# Sparkfun_LilyPad-Switched-Battery.net
KiCad netlist of a schematic drawn in EAGLE
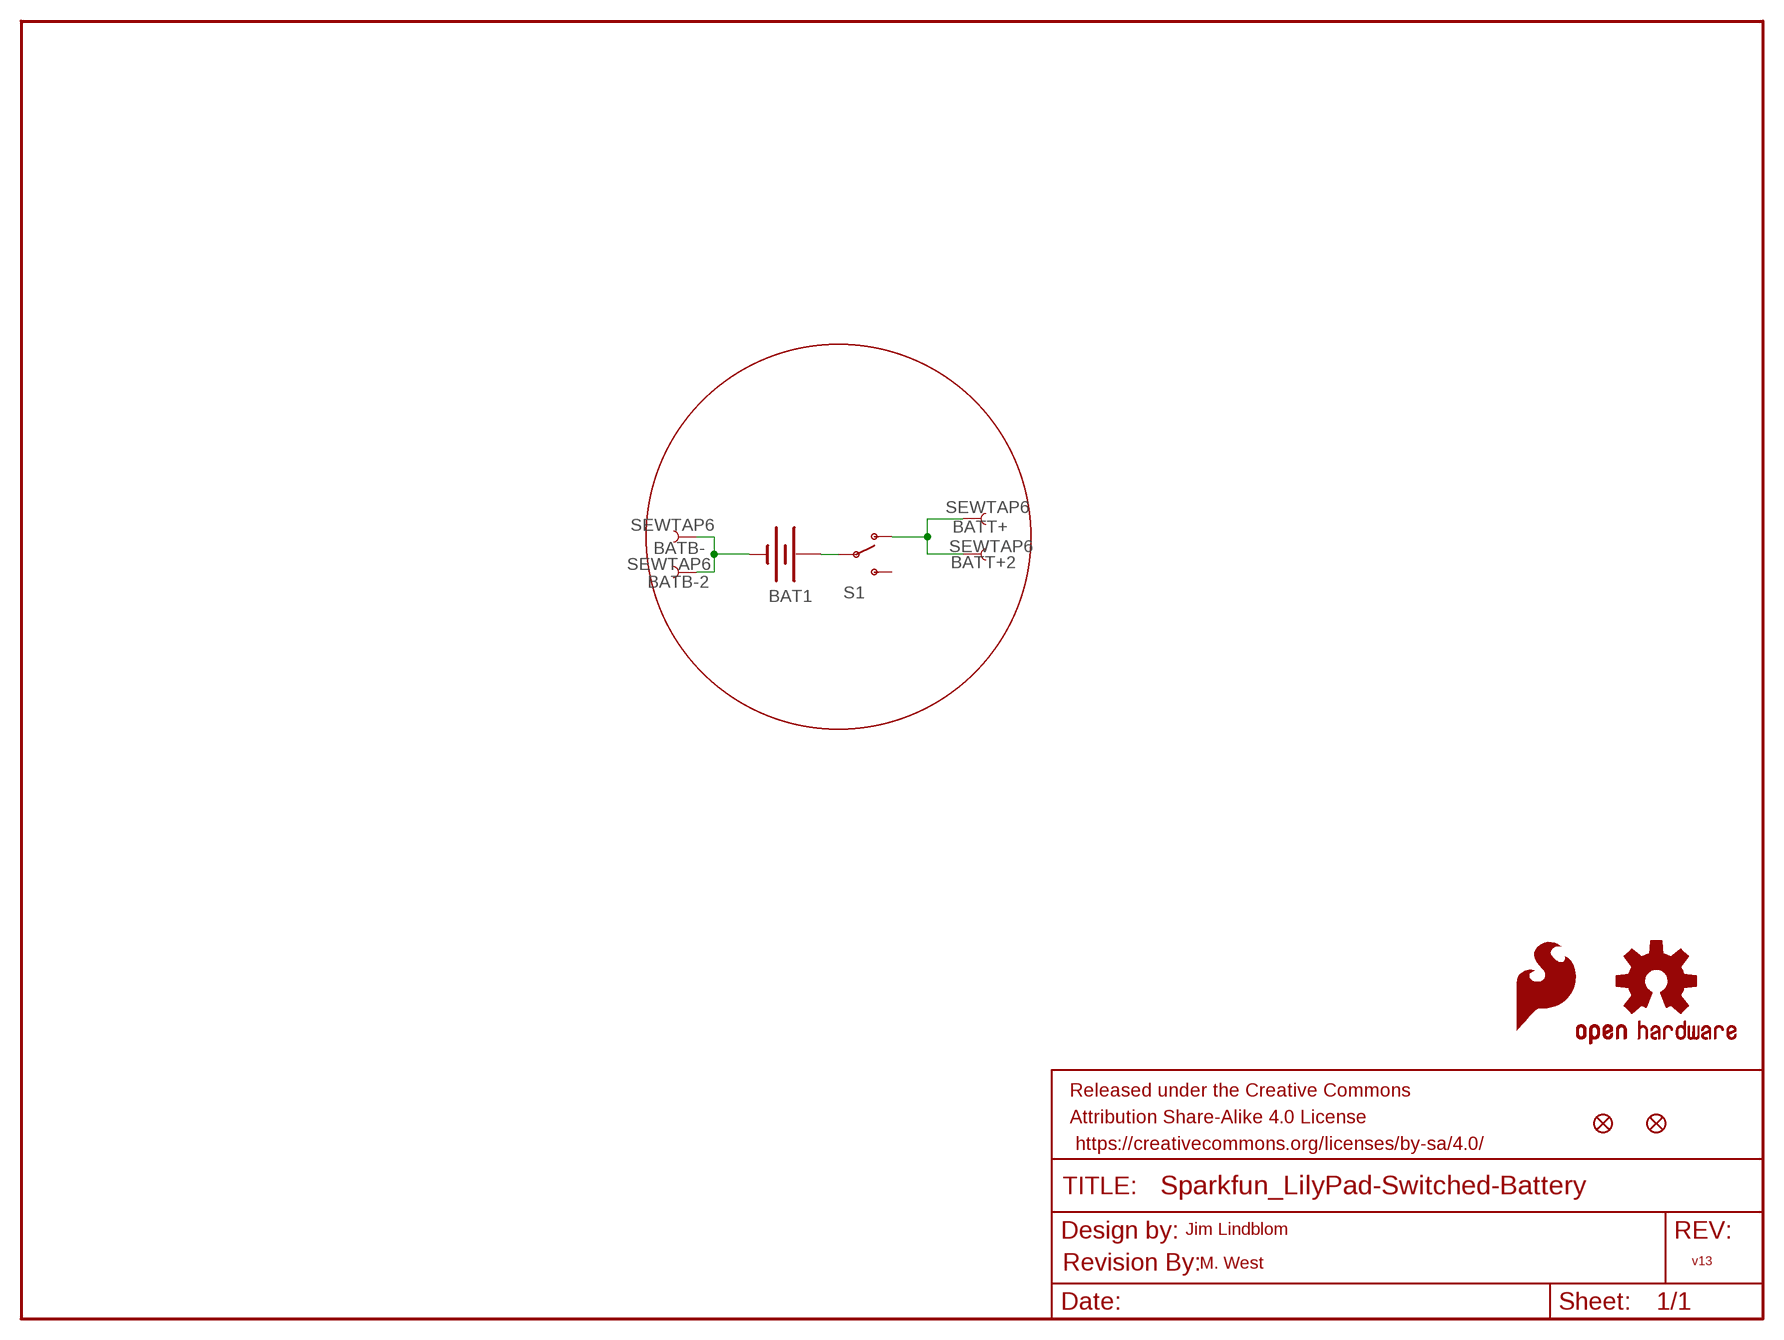
[diagram p0: schematic, sheet 1]

(export (version "E")
  (design (tool "Eeschema 10.0.6"))
  (components
    (comp (ref "BAT1")
      (value "20mm coincell")
      (footprint "eagle-import:BATTCON_20MM_4LEGS")
      (libsource (lib "eagle-import") (part "BATTERY20MM_4LEGS"))
    )
    (comp (ref "BATB-")
      (value "SEWTAP6")
      (footprint "eagle-import:PETAL-SMALL-2SIDE")
      (libsource (lib "eagle-import") (part "SEWTAP6"))
    )
    (comp (ref "BATB-2")
      (value "SEWTAP6")
      (footprint "eagle-import:PETAL-SMALL-2SIDE")
      (libsource (lib "eagle-import") (part "SEWTAP6"))
    )
    (comp (ref "BATT+")
      (value "SEWTAP6")
      (footprint "eagle-import:PETAL-SMALL-2SIDE")
      (libsource (lib "eagle-import") (part "SEWTAP6"))
    )
    (comp (ref "BATT+2")
      (value "SEWTAP6")
      (footprint "eagle-import:PETAL-SMALL-2SIDE")
      (libsource (lib "eagle-import") (part "SEWTAP6"))
    )
    (comp (ref "FD1")
      (value "FIDUCIALUFIDUCIAL")
      (footprint "eagle-import:MICRO-FIDUCIAL")
      (libsource (lib "eagle-import") (part "FIDUCIALUFIDUCIAL"))
    )
    (comp (ref "FD2")
      (value "FIDUCIALUFIDUCIAL")
      (footprint "eagle-import:MICRO-FIDUCIAL")
      (libsource (lib "eagle-import") (part "FIDUCIALUFIDUCIAL"))
    )
    (comp (ref "FRAME1")
      (value "FRAME-LETTER")
      (footprint "eagle-import:CREATIVE_COMMONS")
      (libsource (lib "eagle-import") (part "FRAME-LETTER"))
    )
    (comp (ref "LOGO1")
      (value "SFE_LOGO_FLAME.1_INCH")
      (footprint "eagle-import:SFE_LOGO_FLAME_.1")
      (libsource (lib "eagle-import") (part "SFE_LOGO_FLAME.1_INCH"))
    )
    (comp (ref "LOGO2")
      (value "OSHW-LOGOS")
      (footprint "eagle-import:OSHW-LOGO-S")
      (libsource (lib "eagle-import") (part "OSHW-LOGOS"))
    )
    (comp (ref "S1")
      (value "SWITCH-SPDTSMD")
      (footprint "eagle-import:AYZ0202")
      (libsource (lib "eagle-import") (part "SWITCH-SPDTSMD"))
    )
    (comp (ref "U$1")
      (value "REVISION")
      (footprint "eagle-import:REVISION")
      (libsource (lib "eagle-import") (part "REVISION"))
    )
  )
  (nets
    (net (code "1") (name "Net-(BAT1--)") (class "Default")
      (node (ref "BAT1") (pin "NEGATIVE") (pinfunction "-_NEGATIVE") (pintype "power_in"))
      (node (ref "BATB-") (pin "1") (pinfunction "1_1") (pintype "bidirectional"))
      (node (ref "BATB-2") (pin "1") (pinfunction "1_1") (pintype "bidirectional"))
    )
    (net (code "2") (name "Net-(S1-O)") (class "Default")
      (node (ref "BATT+") (pin "1") (pinfunction "1_1") (pintype "bidirectional"))
      (node (ref "BATT+2") (pin "1") (pinfunction "1_1") (pintype "bidirectional"))
      (node (ref "S1") (pin "1") (pinfunction "O_1") (pintype "passive"))
    )
    (net (code "3") (name "Net-(S1-P)") (class "Default")
      (node (ref "BAT1") (pin "POSITIVE@1") (pinfunction "+_POSITIVE@1") (pintype "power_in"))
      (node (ref "BAT1") (pin "POSITIVE@2") (pinfunction "+_POSITIVE@2") (pintype "power_in"))
      (node (ref "BAT1") (pin "POSITIVE@3") (pinfunction "+_POSITIVE@3") (pintype "power_in"))
      (node (ref "BAT1") (pin "POSITIVE@4") (pinfunction "+_POSITIVE@4") (pintype "power_in"))
      (node (ref "S1") (pin "2") (pinfunction "P_2") (pintype "passive"))
    )
    (net (code "4") (name "unconnected-(S1-S-Pad3)") (class "Default")
      (node (ref "S1") (pin "3") (pinfunction "S_3") (pintype "passive"))
    )
  )
)
